# Motors.net
KiCad netlist of a schematic drawn in Altium Designer
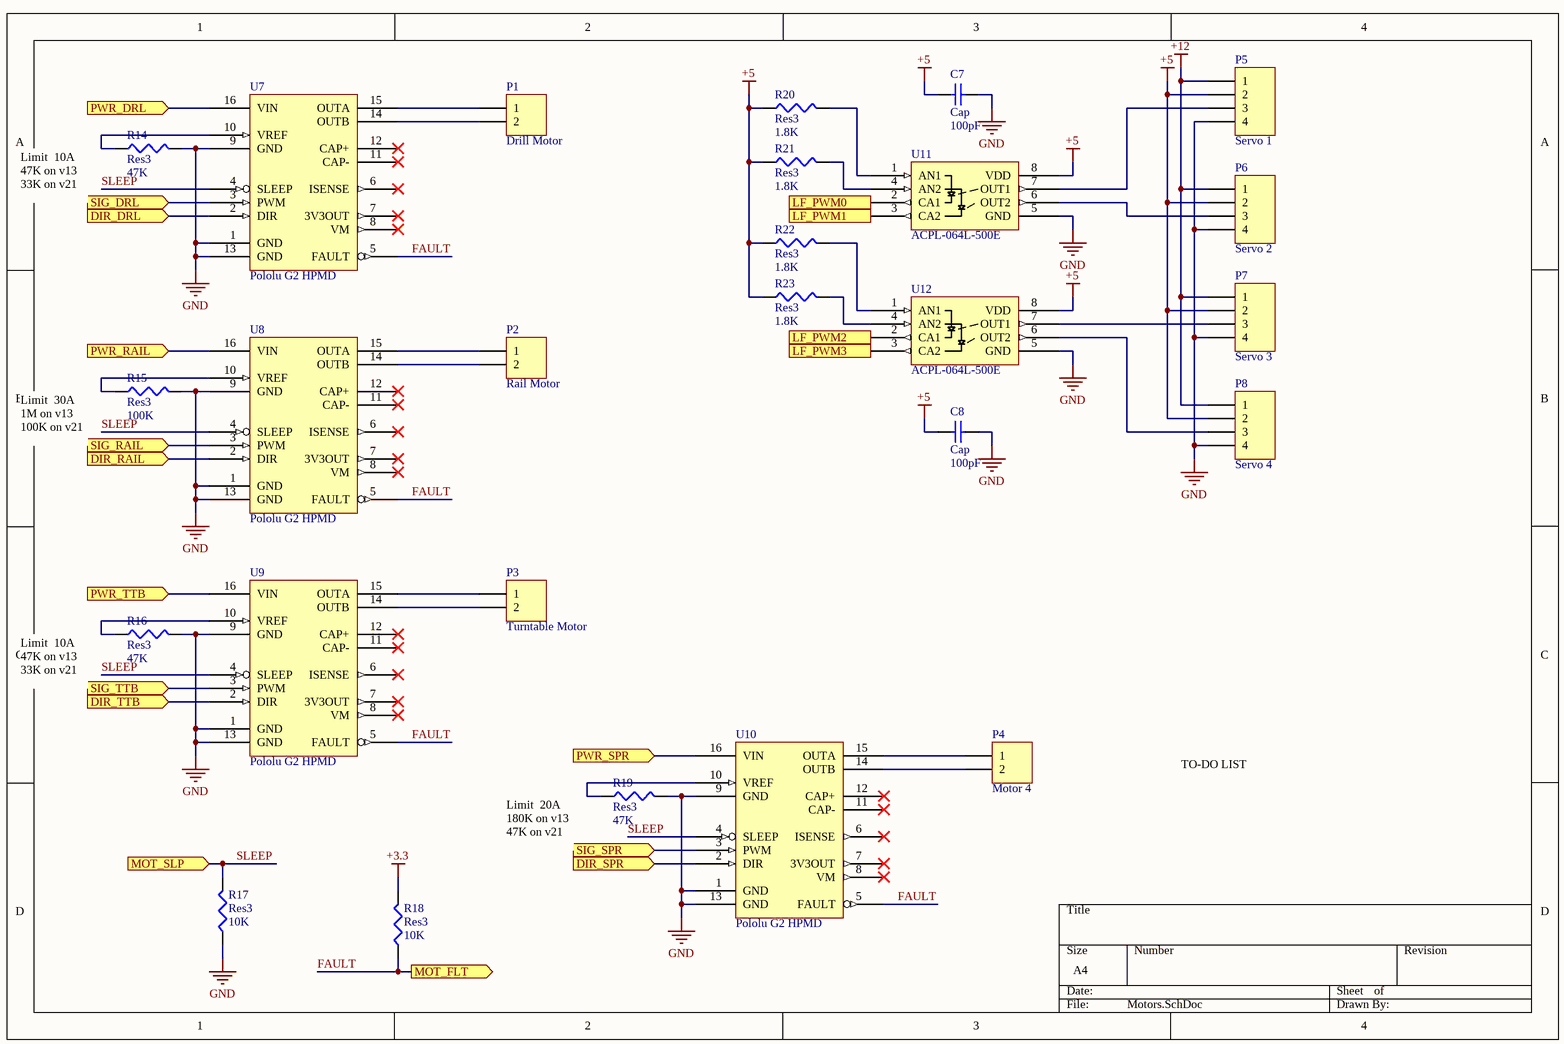
[diagram p0: Motors.SchDoc]

(export (version "E")
  (design (tool "Eeschema 10.0.6"))
  (components
    (comp (ref "C7")
      (value "Cap")
      (footprint "C0805")
      (description "Capacitor")
      (fields (field (name "ALTIUM_VALUE") "100pF") (field (name "PUBLISHER") "Altium Limited"))
      (libsource (lib "Miscellaneous Devices") (part "Cap"))
    )
    (comp (ref "C8")
      (value "Cap")
      (footprint "C0805")
      (description "Capacitor")
      (fields (field (name "ALTIUM_VALUE") "100pF") (field (name "PUBLISHER") "Altium Limited"))
      (libsource (lib "Miscellaneous Devices") (part "Cap"))
    )
    (comp (ref "P1")
      (value "Drill Motor")
      (footprint "Sabre-2pos")
      (description "Header, 2-Pin")
      (fields (field (name "PUBLISHER") "Altium Limited"))
      (libsource (lib "Miscellaneous Connectors") (part "Header 2"))
    )
    (comp (ref "P2")
      (value "Rail Motor")
      (footprint "Sabre-2pos")
      (description "Header, 2-Pin")
      (fields (field (name "PUBLISHER") "Altium Limited"))
      (libsource (lib "Miscellaneous Connectors") (part "Header 2"))
    )
    (comp (ref "P3")
      (value "Turntable Motor")
      (footprint "Sabre-2pos")
      (description "Header, 2-Pin")
      (fields (field (name "PUBLISHER") "Altium Limited"))
      (libsource (lib "Miscellaneous Connectors") (part "Header 2"))
    )
    (comp (ref "P4")
      (value "Motor 4")
      (footprint "Sabre-2pos")
      (description "Header, 2-Pin")
      (fields (field (name "PUBLISHER") "Altium Limited"))
      (libsource (lib "Miscellaneous Connectors") (part "Header 2"))
    )
    (comp (ref "P5")
      (value "Servo 1")
      (footprint "22-23-20x1-4pos")
      (description "Header, 4-Pin")
      (fields (field (name "PUBLISHER") "Altium Limited"))
      (libsource (lib "Miscellaneous Connectors") (part "Header 4"))
    )
    (comp (ref "P6")
      (value "Servo 2")
      (footprint "22-23-20x1-4pos")
      (description "Header, 4-Pin")
      (fields (field (name "PUBLISHER") "Altium Limited"))
      (libsource (lib "Miscellaneous Connectors") (part "Header 4"))
    )
    (comp (ref "P7")
      (value "Servo 3")
      (footprint "22-23-20x1-4pos")
      (description "Header, 4-Pin")
      (fields (field (name "PUBLISHER") "Altium Limited"))
      (libsource (lib "Miscellaneous Connectors") (part "Header 4"))
    )
    (comp (ref "P8")
      (value "Servo 4")
      (footprint "22-23-20x1-4pos")
      (description "Header, 4-Pin")
      (fields (field (name "PUBLISHER") "Altium Limited"))
      (libsource (lib "Miscellaneous Connectors") (part "Header 4"))
    )
    (comp (ref "R14")
      (value "Res3")
      (footprint "C0805")
      (description "Resistor")
      (fields (field (name "ALTIUM_VALUE") "47K") (field (name "PUBLISHER") "Altium Limited"))
      (libsource (lib "Miscellaneous Devices") (part "Res3"))
    )
    (comp (ref "R15")
      (value "Res3")
      (footprint "C0805")
      (description "Resistor")
      (fields (field (name "ALTIUM_VALUE") "100K") (field (name "PUBLISHER") "Altium Limited"))
      (libsource (lib "Miscellaneous Devices") (part "Res3"))
    )
    (comp (ref "R16")
      (value "Res3")
      (footprint "C0805")
      (description "Resistor")
      (fields (field (name "ALTIUM_VALUE") "47K") (field (name "PUBLISHER") "Altium Limited"))
      (libsource (lib "Miscellaneous Devices") (part "Res3"))
    )
    (comp (ref "R17")
      (value "Res3")
      (footprint "C0805")
      (description "Resistor")
      (fields (field (name "ALTIUM_VALUE") "10K") (field (name "PUBLISHER") "Altium Limited"))
      (libsource (lib "Miscellaneous Devices") (part "Res3"))
    )
    (comp (ref "R18")
      (value "Res3")
      (footprint "C0805")
      (description "Resistor")
      (fields (field (name "ALTIUM_VALUE") "10K") (field (name "PUBLISHER") "Altium Limited"))
      (libsource (lib "Miscellaneous Devices") (part "Res3"))
    )
    (comp (ref "R19")
      (value "Res3")
      (footprint "C0805")
      (description "Resistor")
      (fields (field (name "ALTIUM_VALUE") "47K") (field (name "PUBLISHER") "Altium Limited"))
      (libsource (lib "Miscellaneous Devices") (part "Res3"))
    )
    (comp (ref "R20")
      (value "Res3")
      (footprint "C0805")
      (description "Resistor")
      (fields (field (name "ALTIUM_VALUE") "1.8K") (field (name "PUBLISHER") "Altium Limited"))
      (libsource (lib "Miscellaneous Devices") (part "Res3"))
    )
    (comp (ref "R21")
      (value "Res3")
      (footprint "C0805")
      (description "Resistor")
      (fields (field (name "ALTIUM_VALUE") "1.8K") (field (name "PUBLISHER") "Altium Limited"))
      (libsource (lib "Miscellaneous Devices") (part "Res3"))
    )
    (comp (ref "R22")
      (value "Res3")
      (footprint "C0805")
      (description "Resistor")
      (fields (field (name "ALTIUM_VALUE") "1.8K") (field (name "PUBLISHER") "Altium Limited"))
      (libsource (lib "Miscellaneous Devices") (part "Res3"))
    )
    (comp (ref "R23")
      (value "Res3")
      (footprint "C0805")
      (description "Resistor")
      (fields (field (name "ALTIUM_VALUE") "1.8K") (field (name "PUBLISHER") "Altium Limited"))
      (libsource (lib "Miscellaneous Devices") (part "Res3"))
    )
    (comp (ref "U7")
      (value "Pololu G2 HPMD")
      (footprint "Pololu-HPMDG2-SCIENCE")
      (description "Discrete MOSFET H-bridge")
      (libsource (lib "ScienceSymbols") (part "Pololu-G2HPMD"))
    )
    (comp (ref "U8")
      (value "Pololu G2 HPMD")
      (footprint "Pololu-HPMDG2-SCIENCE")
      (description "Discrete MOSFET H-bridge")
      (libsource (lib "ScienceSymbols") (part "Pololu-G2HPMD"))
    )
    (comp (ref "U9")
      (value "Pololu G2 HPMD")
      (footprint "Pololu-HPMDG2-SCIENCE")
      (description "Discrete MOSFET H-bridge")
      (libsource (lib "ScienceSymbols") (part "Pololu-G2HPMD"))
    )
    (comp (ref "U10")
      (value "Pololu G2 HPMD")
      (footprint "Pololu-HPMDG2-SCIENCE")
      (description "Discrete MOSFET H-bridge")
      (libsource (lib "ScienceSymbols") (part "Pololu-G2HPMD"))
    )
    (comp (ref "U11")
      (value "ACPL-064L-500E")
      (footprint "ACPL-064L")
      (description "Low-Power 10-MBd Digital CMOS Optocouplers")
      (libsource (lib "ScienceSymbols") (part "ACPL-064L-500E"))
    )
    (comp (ref "U12")
      (value "ACPL-064L-500E")
      (footprint "ACPL-064L")
      (description "Low-Power 10-MBd Digital CMOS Optocouplers")
      (libsource (lib "ScienceSymbols") (part "ACPL-064L-500E"))
    )
  )
  (nets
    (net (code "1") (name "+3.3") (class "Default")
      (node (ref "R18") (pin "2") (pinfunction "2_2") (pintype "passive"))
    )
    (net (code "2") (name "+5") (class "Default")
      (node (ref "C7") (pin "2") (pinfunction "2_2") (pintype "passive"))
      (node (ref "C8") (pin "2") (pinfunction "2_2") (pintype "passive"))
      (node (ref "P5") (pin "2") (pinfunction "2_2") (pintype "passive"))
      (node (ref "P6") (pin "2") (pinfunction "2_2") (pintype "passive"))
      (node (ref "P7") (pin "2") (pinfunction "2_2") (pintype "passive"))
      (node (ref "P8") (pin "2") (pinfunction "2_2") (pintype "passive"))
      (node (ref "R20") (pin "1") (pinfunction "1_1") (pintype "passive"))
      (node (ref "R21") (pin "1") (pinfunction "1_1") (pintype "passive"))
      (node (ref "R22") (pin "1") (pinfunction "1_1") (pintype "passive"))
      (node (ref "R23") (pin "1") (pinfunction "1_1") (pintype "passive"))
      (node (ref "U11") (pin "8") (pinfunction "VDD_8") (pintype "power_in"))
      (node (ref "U12") (pin "8") (pinfunction "VDD_8") (pintype "power_in"))
    )
    (net (code "3") (name "+12") (class "Default")
      (node (ref "P5") (pin "1") (pinfunction "1_1") (pintype "passive"))
      (node (ref "P6") (pin "1") (pinfunction "1_1") (pintype "passive"))
      (node (ref "P7") (pin "1") (pinfunction "1_1") (pintype "passive"))
      (node (ref "P8") (pin "1") (pinfunction "1_1") (pintype "passive"))
    )
    (net (code "4") (name "/DIR_DRL") (class "Default")
      (node (ref "U7") (pin "2") (pinfunction "DIR_2") (pintype "input"))
    )
    (net (code "5") (name "/DIR_RAIL") (class "Default")
      (node (ref "U8") (pin "2") (pinfunction "DIR_2") (pintype "input"))
    )
    (net (code "6") (name "/DIR_SPR") (class "Default")
      (node (ref "U10") (pin "2") (pinfunction "DIR_2") (pintype "input"))
    )
    (net (code "7") (name "/DIR_TTB") (class "Default")
      (node (ref "U9") (pin "2") (pinfunction "DIR_2") (pintype "input"))
    )
    (net (code "8") (name "/FAULT") (class "Default")
      (node (ref "R18") (pin "1") (pinfunction "1_1") (pintype "passive"))
      (node (ref "U10") (pin "5") (pinfunction "FAULT_5") (pintype "output"))
      (node (ref "U7") (pin "5") (pinfunction "FAULT_5") (pintype "output"))
      (node (ref "U8") (pin "5") (pinfunction "FAULT_5") (pintype "output"))
      (node (ref "U9") (pin "5") (pinfunction "FAULT_5") (pintype "output"))
    )
    (net (code "9") (name "/LF_PWM0") (class "Default")
      (node (ref "U11") (pin "2") (pinfunction "CA1_2") (pintype "output"))
    )
    (net (code "10") (name "/LF_PWM1") (class "Default")
      (node (ref "U11") (pin "3") (pinfunction "CA2_3") (pintype "output"))
    )
    (net (code "11") (name "/LF_PWM2") (class "Default")
      (node (ref "U12") (pin "2") (pinfunction "CA1_2") (pintype "output"))
    )
    (net (code "12") (name "/LF_PWM3") (class "Default")
      (node (ref "U12") (pin "3") (pinfunction "CA2_3") (pintype "output"))
    )
    (net (code "13") (name "/PWR_DRL") (class "Default")
      (node (ref "U7") (pin "16") (pinfunction "VIN_16") (pintype "power_in"))
    )
    (net (code "14") (name "/PWR_RAIL") (class "Default")
      (node (ref "U8") (pin "16") (pinfunction "VIN_16") (pintype "power_in"))
    )
    (net (code "15") (name "/PWR_SPR") (class "Default")
      (node (ref "U10") (pin "16") (pinfunction "VIN_16") (pintype "power_in"))
    )
    (net (code "16") (name "/PWR_TTB") (class "Default")
      (node (ref "U9") (pin "16") (pinfunction "VIN_16") (pintype "power_in"))
    )
    (net (code "17") (name "/SIG_DRL") (class "Default")
      (node (ref "U7") (pin "3") (pinfunction "PWM_3") (pintype "input"))
    )
    (net (code "18") (name "/SIG_RAIL") (class "Default")
      (node (ref "U8") (pin "3") (pinfunction "PWM_3") (pintype "input"))
    )
    (net (code "19") (name "/SIG_SPR") (class "Default")
      (node (ref "U10") (pin "3") (pinfunction "PWM_3") (pintype "input"))
    )
    (net (code "20") (name "/SIG_TTB") (class "Default")
      (node (ref "U9") (pin "3") (pinfunction "PWM_3") (pintype "input"))
    )
    (net (code "21") (name "/SLEEP") (class "Default")
      (node (ref "R17") (pin "2") (pinfunction "2_2") (pintype "passive"))
      (node (ref "U10") (pin "4") (pinfunction "SLEEP_4") (pintype "input"))
      (node (ref "U7") (pin "4") (pinfunction "SLEEP_4") (pintype "input"))
      (node (ref "U8") (pin "4") (pinfunction "SLEEP_4") (pintype "input"))
      (node (ref "U9") (pin "4") (pinfunction "SLEEP_4") (pintype "input"))
    )
    (net (code "22") (name "GND") (class "Default")
      (node (ref "C7") (pin "1") (pinfunction "1_1") (pintype "passive"))
      (node (ref "C8") (pin "1") (pinfunction "1_1") (pintype "passive"))
      (node (ref "P5") (pin "4") (pinfunction "4_4") (pintype "passive"))
      (node (ref "P6") (pin "4") (pinfunction "4_4") (pintype "passive"))
      (node (ref "P7") (pin "4") (pinfunction "4_4") (pintype "passive"))
      (node (ref "P8") (pin "4") (pinfunction "4_4") (pintype "passive"))
      (node (ref "R14") (pin "2") (pinfunction "2_2") (pintype "passive"))
      (node (ref "R15") (pin "2") (pinfunction "2_2") (pintype "passive"))
      (node (ref "R16") (pin "2") (pinfunction "2_2") (pintype "passive"))
      (node (ref "R17") (pin "1") (pinfunction "1_1") (pintype "passive"))
      (node (ref "R19") (pin "2") (pinfunction "2_2") (pintype "passive"))
      (node (ref "U10") (pin "1") (pinfunction "GND_1") (pintype "power_in"))
      (node (ref "U10") (pin "13") (pinfunction "GND_13") (pintype "power_in"))
      (node (ref "U10") (pin "9") (pinfunction "GND_9") (pintype "power_in"))
      (node (ref "U11") (pin "5") (pinfunction "GND_5") (pintype "power_in"))
      (node (ref "U12") (pin "5") (pinfunction "GND_5") (pintype "power_in"))
      (node (ref "U7") (pin "1") (pinfunction "GND_1") (pintype "power_in"))
      (node (ref "U7") (pin "13") (pinfunction "GND_13") (pintype "power_in"))
      (node (ref "U7") (pin "9") (pinfunction "GND_9") (pintype "power_in"))
      (node (ref "U8") (pin "1") (pinfunction "GND_1") (pintype "power_in"))
      (node (ref "U8") (pin "13") (pinfunction "GND_13") (pintype "power_in"))
      (node (ref "U8") (pin "9") (pinfunction "GND_9") (pintype "power_in"))
      (node (ref "U9") (pin "1") (pinfunction "GND_1") (pintype "power_in"))
      (node (ref "U9") (pin "13") (pinfunction "GND_13") (pintype "power_in"))
      (node (ref "U9") (pin "9") (pinfunction "GND_9") (pintype "power_in"))
    )
    (net (code "23") (name "Net-(U7-OUTA)") (class "Default")
      (node (ref "P1") (pin "1") (pinfunction "1_1") (pintype "passive"))
      (node (ref "U7") (pin "15") (pinfunction "OUTA_15") (pintype "power_in"))
    )
    (net (code "24") (name "Net-(U7-OUTB)") (class "Default")
      (node (ref "P1") (pin "2") (pinfunction "2_2") (pintype "passive"))
      (node (ref "U7") (pin "14") (pinfunction "OUTB_14") (pintype "power_in"))
    )
    (net (code "25") (name "Net-(U7-VREF)") (class "Default")
      (node (ref "R14") (pin "1") (pinfunction "1_1") (pintype "passive"))
      (node (ref "U7") (pin "10") (pinfunction "VREF_10") (pintype "input"))
    )
    (net (code "26") (name "Net-(U8-OUTA)") (class "Default")
      (node (ref "P2") (pin "1") (pinfunction "1_1") (pintype "passive"))
      (node (ref "U8") (pin "15") (pinfunction "OUTA_15") (pintype "power_in"))
    )
    (net (code "27") (name "Net-(U8-OUTB)") (class "Default")
      (node (ref "P2") (pin "2") (pinfunction "2_2") (pintype "passive"))
      (node (ref "U8") (pin "14") (pinfunction "OUTB_14") (pintype "power_in"))
    )
    (net (code "28") (name "Net-(U8-VREF)") (class "Default")
      (node (ref "R15") (pin "1") (pinfunction "1_1") (pintype "passive"))
      (node (ref "U8") (pin "10") (pinfunction "VREF_10") (pintype "input"))
    )
    (net (code "29") (name "Net-(U9-OUTA)") (class "Default")
      (node (ref "P3") (pin "1") (pinfunction "1_1") (pintype "passive"))
      (node (ref "U9") (pin "15") (pinfunction "OUTA_15") (pintype "power_in"))
    )
    (net (code "30") (name "Net-(U9-OUTB)") (class "Default")
      (node (ref "P3") (pin "2") (pinfunction "2_2") (pintype "passive"))
      (node (ref "U9") (pin "14") (pinfunction "OUTB_14") (pintype "power_in"))
    )
    (net (code "31") (name "Net-(U9-VREF)") (class "Default")
      (node (ref "R16") (pin "1") (pinfunction "1_1") (pintype "passive"))
      (node (ref "U9") (pin "10") (pinfunction "VREF_10") (pintype "input"))
    )
    (net (code "32") (name "Net-(U10-OUTA)") (class "Default")
      (node (ref "P4") (pin "1") (pinfunction "1_1") (pintype "passive"))
      (node (ref "U10") (pin "15") (pinfunction "OUTA_15") (pintype "power_in"))
    )
    (net (code "33") (name "Net-(U10-OUTB)") (class "Default")
      (node (ref "P4") (pin "2") (pinfunction "2_2") (pintype "passive"))
      (node (ref "U10") (pin "14") (pinfunction "OUTB_14") (pintype "power_in"))
    )
    (net (code "34") (name "Net-(U10-VREF)") (class "Default")
      (node (ref "R19") (pin "1") (pinfunction "1_1") (pintype "passive"))
      (node (ref "U10") (pin "10") (pinfunction "VREF_10") (pintype "input"))
    )
    (net (code "35") (name "Net-(U11-AN1)") (class "Default")
      (node (ref "R20") (pin "2") (pinfunction "2_2") (pintype "passive"))
      (node (ref "U11") (pin "1") (pinfunction "AN1_1") (pintype "input"))
    )
    (net (code "36") (name "Net-(U11-AN2)") (class "Default")
      (node (ref "R21") (pin "2") (pinfunction "2_2") (pintype "passive"))
      (node (ref "U11") (pin "4") (pinfunction "AN2_4") (pintype "input"))
    )
    (net (code "37") (name "Net-(U11-OUT1)") (class "Default")
      (node (ref "P5") (pin "3") (pinfunction "3_3") (pintype "passive"))
      (node (ref "U11") (pin "7") (pinfunction "OUT1_7") (pintype "output"))
    )
    (net (code "38") (name "Net-(U11-OUT2)") (class "Default")
      (node (ref "P6") (pin "3") (pinfunction "3_3") (pintype "passive"))
      (node (ref "U11") (pin "6") (pinfunction "OUT2_6") (pintype "output"))
    )
    (net (code "39") (name "Net-(U12-AN1)") (class "Default")
      (node (ref "R22") (pin "2") (pinfunction "2_2") (pintype "passive"))
      (node (ref "U12") (pin "1") (pinfunction "AN1_1") (pintype "input"))
    )
    (net (code "40") (name "Net-(U12-AN2)") (class "Default")
      (node (ref "R23") (pin "2") (pinfunction "2_2") (pintype "passive"))
      (node (ref "U12") (pin "4") (pinfunction "AN2_4") (pintype "input"))
    )
    (net (code "41") (name "Net-(U12-OUT1)") (class "Default")
      (node (ref "P7") (pin "3") (pinfunction "3_3") (pintype "passive"))
      (node (ref "U12") (pin "7") (pinfunction "OUT1_7") (pintype "output"))
    )
    (net (code "42") (name "Net-(U12-OUT2)") (class "Default")
      (node (ref "P8") (pin "3") (pinfunction "3_3") (pintype "passive"))
      (node (ref "U12") (pin "6") (pinfunction "OUT2_6") (pintype "output"))
    )
    (net (code "43") (name "unconnected-(U7-3V3OUT-Pad7)") (class "Default")
      (node (ref "U7") (pin "7") (pinfunction "3V3OUT_7") (pintype "output+no_connect"))
    )
    (net (code "44") (name "unconnected-(U7-CAP+-Pad12)") (class "Default")
      (node (ref "U7") (pin "12") (pinfunction "CAP+_12") (pintype "power_in+no_connect"))
    )
    (net (code "45") (name "unconnected-(U7-CAP--Pad11)") (class "Default")
      (node (ref "U7") (pin "11") (pinfunction "CAP-_11") (pintype "power_in+no_connect"))
    )
    (net (code "46") (name "unconnected-(U7-ISENSE-Pad6)") (class "Default")
      (node (ref "U7") (pin "6") (pinfunction "ISENSE_6") (pintype "output+no_connect"))
    )
    (net (code "47") (name "unconnected-(U7-VM-Pad8)") (class "Default")
      (node (ref "U7") (pin "8") (pinfunction "VM_8") (pintype "output+no_connect"))
    )
    (net (code "48") (name "unconnected-(U8-3V3OUT-Pad7)") (class "Default")
      (node (ref "U8") (pin "7") (pinfunction "3V3OUT_7") (pintype "output+no_connect"))
    )
    (net (code "49") (name "unconnected-(U8-CAP+-Pad12)") (class "Default")
      (node (ref "U8") (pin "12") (pinfunction "CAP+_12") (pintype "power_in+no_connect"))
    )
    (net (code "50") (name "unconnected-(U8-CAP--Pad11)") (class "Default")
      (node (ref "U8") (pin "11") (pinfunction "CAP-_11") (pintype "power_in+no_connect"))
    )
    (net (code "51") (name "unconnected-(U8-ISENSE-Pad6)") (class "Default")
      (node (ref "U8") (pin "6") (pinfunction "ISENSE_6") (pintype "output+no_connect"))
    )
    (net (code "52") (name "unconnected-(U8-VM-Pad8)") (class "Default")
      (node (ref "U8") (pin "8") (pinfunction "VM_8") (pintype "output+no_connect"))
    )
    (net (code "53") (name "unconnected-(U9-3V3OUT-Pad7)") (class "Default")
      (node (ref "U9") (pin "7") (pinfunction "3V3OUT_7") (pintype "output+no_connect"))
    )
    (net (code "54") (name "unconnected-(U9-CAP+-Pad12)") (class "Default")
      (node (ref "U9") (pin "12") (pinfunction "CAP+_12") (pintype "power_in+no_connect"))
    )
    (net (code "55") (name "unconnected-(U9-CAP--Pad11)") (class "Default")
      (node (ref "U9") (pin "11") (pinfunction "CAP-_11") (pintype "power_in+no_connect"))
    )
    (net (code "56") (name "unconnected-(U9-ISENSE-Pad6)") (class "Default")
      (node (ref "U9") (pin "6") (pinfunction "ISENSE_6") (pintype "output+no_connect"))
    )
    (net (code "57") (name "unconnected-(U9-VM-Pad8)") (class "Default")
      (node (ref "U9") (pin "8") (pinfunction "VM_8") (pintype "output+no_connect"))
    )
    (net (code "58") (name "unconnected-(U10-3V3OUT-Pad7)") (class "Default")
      (node (ref "U10") (pin "7") (pinfunction "3V3OUT_7") (pintype "output+no_connect"))
    )
    (net (code "59") (name "unconnected-(U10-CAP+-Pad12)") (class "Default")
      (node (ref "U10") (pin "12") (pinfunction "CAP+_12") (pintype "power_in+no_connect"))
    )
    (net (code "60") (name "unconnected-(U10-CAP--Pad11)") (class "Default")
      (node (ref "U10") (pin "11") (pinfunction "CAP-_11") (pintype "power_in+no_connect"))
    )
    (net (code "61") (name "unconnected-(U10-ISENSE-Pad6)") (class "Default")
      (node (ref "U10") (pin "6") (pinfunction "ISENSE_6") (pintype "output+no_connect"))
    )
    (net (code "62") (name "unconnected-(U10-VM-Pad8)") (class "Default")
      (node (ref "U10") (pin "8") (pinfunction "VM_8") (pintype "output+no_connect"))
    )
  )
)
